# M_Driver.net
KiCad netlist of a schematic drawn in Altium Designer
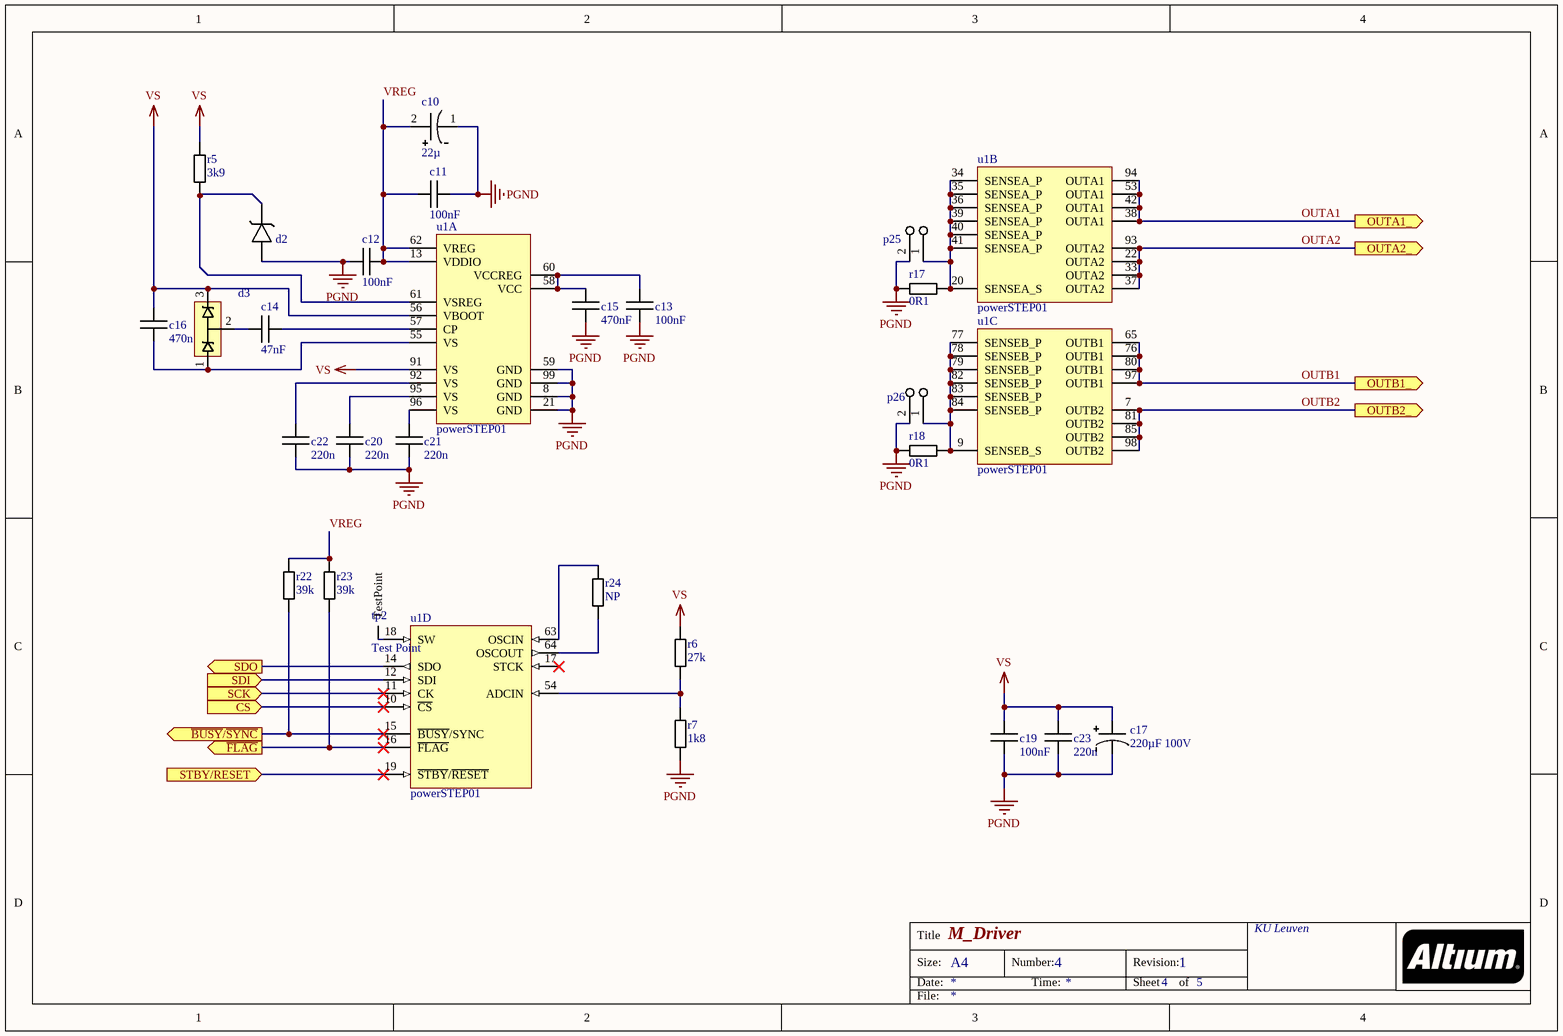
[diagram p0: M_Driver.SchDoc]

(export (version "E")
  (design (tool "Eeschema 10.0.6"))
  (components
    (comp (ref "c10") (value "22µ") (footprint "Elco-B") (libsource (lib "Panasonic") (part "Elco B")))
    (comp (ref "c11")
      (value "100nF")
      (footprint "0805")
      (description "...F")
      (libsource (lib "Generic R-C") (part "0805 Capacitor"))
    )
    (comp (ref "c12")
      (value "100nF")
      (footprint "0805")
      (description "...F")
      (libsource (lib "Generic R-C") (part "0805 Capacitor"))
    )
    (comp (ref "c13")
      (value "100nF")
      (footprint "0805")
      (description "...F")
      (libsource (lib "Generic R-C") (part "0805 Capacitor"))
    )
    (comp (ref "c14")
      (value "47nF")
      (footprint "0805")
      (description "...F")
      (libsource (lib "Generic R-C") (part "0805 Capacitor"))
    )
    (comp (ref "c15")
      (value "470nF")
      (footprint "0805")
      (description "...F")
      (libsource (lib "Generic R-C") (part "0805 Capacitor"))
    )
    (comp (ref "c16")
      (value "470n")
      (footprint "0805")
      (description "...F")
      (libsource (lib "Generic R-C") (part "0805 Capacitor"))
    )
    (comp (ref "c17")
      (value "220µF 100V")
      (footprint "TH Elco 12.5")
      (description "d = 12.5mm")
      (libsource (lib "Panasonic") (part "Elco TH d12.5"))
    )
    (comp (ref "c19")
      (value "100nF")
      (footprint "0805")
      (description "...F")
      (libsource (lib "Generic R-C") (part "0805 Capacitor"))
    )
    (comp (ref "c20")
      (value "220n")
      (footprint "0805")
      (description "...F")
      (libsource (lib "Generic R-C") (part "0805 Capacitor"))
    )
    (comp (ref "c21")
      (value "220n")
      (footprint "0805")
      (description "...F")
      (libsource (lib "Generic R-C") (part "0805 Capacitor"))
    )
    (comp (ref "c22")
      (value "220n")
      (footprint "0805")
      (description "...F")
      (libsource (lib "Generic R-C") (part "0805 Capacitor"))
    )
    (comp (ref "c23")
      (value "220n")
      (footprint "0805")
      (description "...F")
      (libsource (lib "Generic R-C") (part "0805 Capacitor"))
    )
    (comp (ref "d2")
      (value "DZ2W22000L")
      (footprint "Mini2-F3-B")
      (description "Zener diode")
      (libsource (lib "Panasonic") (part "DZ2W22000L"))
    )
    (comp (ref "d3") (value "BAS40-04") (footprint "SOT23") (libsource (lib "Diodes_inc") (part "BAS40-04")))
    (comp (ref "p25")
      (value "2 Pin Header")
      (footprint "1x2-HeaderPin")
      (libsource (lib "Multicomp") (part "2 Pin Header"))
    )
    (comp (ref "p26")
      (value "2 Pin Header")
      (footprint "1x2-HeaderPin")
      (libsource (lib "Multicomp") (part "2 Pin Header"))
    )
    (comp (ref "r5")
      (value "3k9")
      (footprint "1206")
      (description "..R")
      (libsource (lib "Generic R-C") (part "1206 Resistor"))
    )
    (comp (ref "r6")
      (value "27k")
      (footprint "0805")
      (description "...R")
      (libsource (lib "Generic R-C") (part "0805 Resistor"))
    )
    (comp (ref "r7")
      (value "1k8")
      (footprint "0805")
      (description "...R")
      (libsource (lib "Generic R-C") (part "0805 Resistor"))
    )
    (comp (ref "r17")
      (value "0R1")
      (footprint "2512")
      (description "..R")
      (libsource (lib "Generic R-C") (part "2512 Resistor"))
    )
    (comp (ref "r18")
      (value "0R1")
      (footprint "2512")
      (description "..R")
      (libsource (lib "Generic R-C") (part "2512 Resistor"))
    )
    (comp (ref "r22")
      (value "39k")
      (footprint "0805")
      (description "...R")
      (libsource (lib "Generic R-C") (part "0805 Resistor"))
    )
    (comp (ref "r23")
      (value "39k")
      (footprint "0805")
      (description "...R")
      (libsource (lib "Generic R-C") (part "0805 Resistor"))
    )
    (comp (ref "r24")
      (value "NP")
      (footprint "0603")
      (description "...R")
      (libsource (lib "Generic R-C") (part "0603 Resistor"))
    )
    (comp (ref "tp2")
      (value "Test Point")
      (footprint "Test Point")
      (libsource (lib "Board_Props") (part "Test Point"))
    )
    (comp (ref "u1")
      (value "powerSTEP01")
      (footprint "VFQFPN")
      (description "VFQFPN")
      (libsource (lib "STMicroelectronics") (part "powerSTEP01"))
    )
  )
  (nets
    (net (code "1") (name "/CS") (class "Default")
      (node (ref "u1") (pin "10") (pinfunction "~{CS}_10") (pintype "input+no_connect"))
    )
    (net (code "2") (name "/OUTA1") (class "Default")
      (node (ref "u1") (pin "38") (pinfunction "OUTA1_38") (pintype "passive"))
      (node (ref "u1") (pin "42") (pinfunction "OUTA1_42") (pintype "passive"))
      (node (ref "u1") (pin "53") (pinfunction "OUTA1_53") (pintype "passive"))
      (node (ref "u1") (pin "94") (pinfunction "OUTA1_94") (pintype "passive"))
    )
    (net (code "3") (name "/OUTA2") (class "Default")
      (node (ref "u1") (pin "22") (pinfunction "OUTA2_22") (pintype "passive"))
      (node (ref "u1") (pin "33") (pinfunction "OUTA2_33") (pintype "passive"))
      (node (ref "u1") (pin "37") (pinfunction "OUTA2_37") (pintype "passive"))
      (node (ref "u1") (pin "93") (pinfunction "OUTA2_93") (pintype "passive"))
    )
    (net (code "4") (name "/OUTB1") (class "Default")
      (node (ref "u1") (pin "65") (pinfunction "OUTB1_65") (pintype "passive"))
      (node (ref "u1") (pin "76") (pinfunction "OUTB1_76") (pintype "passive"))
      (node (ref "u1") (pin "80") (pinfunction "OUTB1_80") (pintype "passive"))
      (node (ref "u1") (pin "97") (pinfunction "OUTB1_97") (pintype "passive"))
    )
    (net (code "5") (name "/OUTB2") (class "Default")
      (node (ref "u1") (pin "7") (pinfunction "OUTB2_7") (pintype "passive"))
      (node (ref "u1") (pin "81") (pinfunction "OUTB2_81") (pintype "passive"))
      (node (ref "u1") (pin "85") (pinfunction "OUTB2_85") (pintype "passive"))
      (node (ref "u1") (pin "98") (pinfunction "OUTB2_98") (pintype "passive"))
    )
    (net (code "6") (name "/SCK") (class "Default")
      (node (ref "u1") (pin "11") (pinfunction "CK_11") (pintype "input+no_connect"))
    )
    (net (code "7") (name "/SDI") (class "Default")
      (node (ref "u1") (pin "12") (pinfunction "SDI_12") (pintype "input"))
    )
    (net (code "8") (name "/SDO") (class "Default")
      (node (ref "u1") (pin "14") (pinfunction "SDO_14") (pintype "output"))
    )
    (net (code "9") (name "/STBY{slash}RESET") (class "Default")
      (node (ref "u1") (pin "19") (pinfunction "~{STBY}/~{RESET}_19") (pintype "input+no_connect"))
    )
    (net (code "10") (name "/VREG") (class "Default")
      (node (ref "c10") (pin "2") (pintype "passive"))
      (node (ref "c11") (pin "2") (pintype "passive"))
      (node (ref "c12") (pin "1") (pintype "passive"))
      (node (ref "r22") (pin "1") (pintype "passive"))
      (node (ref "r23") (pin "1") (pintype "passive"))
      (node (ref "u1") (pin "13") (pinfunction "VDDIO_13") (pintype "power_in"))
      (node (ref "u1") (pin "62") (pinfunction "VREG_62") (pintype "power_in"))
    )
    (net (code "11") (name "/~{BUSY}{slash}~{SYNC}") (class "Default")
      (node (ref "r22") (pin "2") (pintype "passive"))
      (node (ref "u1") (pin "15") (pinfunction "~{BUSY}/SYNC_15") (pintype "open_collector"))
    )
    (net (code "12") (name "/~{FLAG}") (class "Default")
      (node (ref "r23") (pin "2") (pintype "passive"))
      (node (ref "u1") (pin "16") (pinfunction "~{FLAG}_16") (pintype "open_collector"))
    )
    (net (code "13") (name "Net-(c14-Pad1)") (class "Default")
      (node (ref "c14") (pin "1") (pintype "passive"))
      (node (ref "d3") (pin "2") (pinfunction "2_2") (pintype "passive"))
    )
    (net (code "14") (name "Net-(c16-Pad2)") (class "Default")
      (node (ref "c16") (pin "2") (pintype "passive"))
      (node (ref "d3") (pin "1") (pinfunction "1_1") (pintype "passive"))
      (node (ref "u1") (pin "55") (pinfunction "VS_55") (pintype "power_in"))
    )
    (net (code "15") (name "Net-(c20-Pad1)") (class "Default")
      (node (ref "c20") (pin "1") (pintype "passive"))
      (node (ref "u1") (pin "95") (pinfunction "VS_95") (pintype "power_in"))
    )
    (net (code "16") (name "Net-(c21-Pad1)") (class "Default")
      (node (ref "c21") (pin "1") (pintype "passive"))
      (node (ref "u1") (pin "96") (pinfunction "VS_96") (pintype "power_in"))
    )
    (net (code "17") (name "Net-(c22-Pad1)") (class "Default")
      (node (ref "c22") (pin "1") (pintype "passive"))
      (node (ref "u1") (pin "92") (pinfunction "VS_92") (pintype "power_in"))
    )
    (net (code "18") (name "Net-(d2-Kathode)") (class "Default")
      (node (ref "d2") (pin "1") (pinfunction "Kathode_1") (pintype "passive"))
      (node (ref "r5") (pin "2") (pintype "passive"))
      (node (ref "u1") (pin "61") (pinfunction "VSREG_61") (pintype "power_in"))
    )
    (net (code "19") (name "Net-(tp2-TestPoint)") (class "Default")
      (node (ref "tp2") (pin "1") (pinfunction "TestPoint_1") (pintype "passive"))
      (node (ref "u1") (pin "18") (pinfunction "SW_18") (pintype "input"))
    )
    (net (code "20") (name "Net-(u1A-CP)") (class "Default")
      (node (ref "c14") (pin "2") (pintype "passive"))
      (node (ref "u1") (pin "57") (pinfunction "CP_57") (pintype "power_in"))
    )
    (net (code "21") (name "Net-(u1A-VCC)") (class "Default")
      (node (ref "c13") (pin "2") (pintype "passive"))
      (node (ref "c15") (pin "2") (pintype "passive"))
      (node (ref "u1") (pin "58") (pinfunction "VCC_58") (pintype "power_in"))
      (node (ref "u1") (pin "60") (pinfunction "VCCREG_60") (pintype "power_in"))
    )
    (net (code "22") (name "Net-(u1B-SENSEA_S)") (class "Default")
      (node (ref "p25") (pin "1") (pinfunction "1_1") (pintype "passive"))
      (node (ref "r17") (pin "2") (pintype "passive"))
      (node (ref "u1") (pin "20") (pinfunction "SENSEA_S_20") (pintype "power_in"))
      (node (ref "u1") (pin "34") (pinfunction "SENSEA_P_34") (pintype "power_in"))
      (node (ref "u1") (pin "35") (pinfunction "SENSEA_P_35") (pintype "power_in"))
      (node (ref "u1") (pin "36") (pinfunction "SENSEA_P_36") (pintype "power_in"))
      (node (ref "u1") (pin "39") (pinfunction "SENSEA_P_39") (pintype "power_in"))
      (node (ref "u1") (pin "40") (pinfunction "SENSEA_P_40") (pintype "power_in"))
      (node (ref "u1") (pin "41") (pinfunction "SENSEA_P_41") (pintype "power_in"))
    )
    (net (code "23") (name "Net-(u1C-SENSEB_S)") (class "Default")
      (node (ref "p26") (pin "1") (pinfunction "1_1") (pintype "passive"))
      (node (ref "r18") (pin "2") (pintype "passive"))
      (node (ref "u1") (pin "77") (pinfunction "SENSEB_P_77") (pintype "power_in"))
      (node (ref "u1") (pin "78") (pinfunction "SENSEB_P_78") (pintype "power_in"))
      (node (ref "u1") (pin "79") (pinfunction "SENSEB_P_79") (pintype "power_in"))
      (node (ref "u1") (pin "82") (pinfunction "SENSEB_P_82") (pintype "power_in"))
      (node (ref "u1") (pin "83") (pinfunction "SENSEB_P_83") (pintype "power_in"))
      (node (ref "u1") (pin "84") (pinfunction "SENSEB_P_84") (pintype "power_in"))
      (node (ref "u1") (pin "9") (pinfunction "SENSEB_S_9") (pintype "power_in"))
    )
    (net (code "24") (name "Net-(u1D-ADCIN)") (class "Default")
      (node (ref "r6") (pin "1") (pintype "passive"))
      (node (ref "r7") (pin "2") (pintype "passive"))
      (node (ref "u1") (pin "54") (pinfunction "ADCIN_54") (pintype "input"))
    )
    (net (code "25") (name "Net-(u1D-OSCIN)") (class "Default")
      (node (ref "r24") (pin "2") (pintype "passive"))
      (node (ref "u1") (pin "63") (pinfunction "OSCIN_63") (pintype "input"))
    )
    (net (code "26") (name "Net-(u1D-OSCOUT)") (class "Default")
      (node (ref "r24") (pin "1") (pintype "passive"))
      (node (ref "u1") (pin "64") (pinfunction "OSCOUT_64") (pintype "output"))
    )
    (net (code "27") (name "PGND") (class "Default")
      (node (ref "c10") (pin "1") (pintype "passive"))
      (node (ref "c11") (pin "1") (pintype "passive"))
      (node (ref "c12") (pin "2") (pintype "passive"))
      (node (ref "c13") (pin "1") (pintype "passive"))
      (node (ref "c15") (pin "1") (pintype "passive"))
      (node (ref "c17") (pin "1") (pintype "passive"))
      (node (ref "c19") (pin "1") (pintype "passive"))
      (node (ref "c20") (pin "2") (pintype "passive"))
      (node (ref "c21") (pin "2") (pintype "passive"))
      (node (ref "c22") (pin "2") (pintype "passive"))
      (node (ref "c23") (pin "2") (pintype "passive"))
      (node (ref "d2") (pin "2") (pinfunction "Anode_2") (pintype "passive"))
      (node (ref "p25") (pin "2") (pinfunction "2_2") (pintype "passive"))
      (node (ref "p26") (pin "2") (pinfunction "2_2") (pintype "passive"))
      (node (ref "r17") (pin "1") (pintype "passive"))
      (node (ref "r18") (pin "1") (pintype "passive"))
      (node (ref "r7") (pin "1") (pintype "passive"))
      (node (ref "u1") (pin "21") (pinfunction "GND_21") (pintype "power_in"))
      (node (ref "u1") (pin "59") (pinfunction "GND_59") (pintype "power_in"))
      (node (ref "u1") (pin "8") (pinfunction "GND_8") (pintype "power_in"))
      (node (ref "u1") (pin "99") (pinfunction "GND_99") (pintype "power_in"))
    )
    (net (code "28") (name "VS") (class "Default")
      (node (ref "c16") (pin "1") (pintype "passive"))
      (node (ref "c17") (pin "2") (pintype "passive"))
      (node (ref "c19") (pin "2") (pintype "passive"))
      (node (ref "c23") (pin "1") (pintype "passive"))
      (node (ref "d3") (pin "3") (pinfunction "3_3") (pintype "passive"))
      (node (ref "r5") (pin "1") (pintype "passive"))
      (node (ref "r6") (pin "2") (pintype "passive"))
      (node (ref "u1") (pin "56") (pinfunction "VBOOT_56") (pintype "power_in"))
      (node (ref "u1") (pin "91") (pinfunction "VS_91") (pintype "power_in"))
    )
    (net (code "29") (name "unconnected-(u1D-STCK-Pad17)") (class "Default")
      (node (ref "u1") (pin "17") (pinfunction "STCK_17") (pintype "input+no_connect"))
    )
  )
)
